# MCU_POWER.net
KiCad netlist of a schematic drawn in Altium Designer
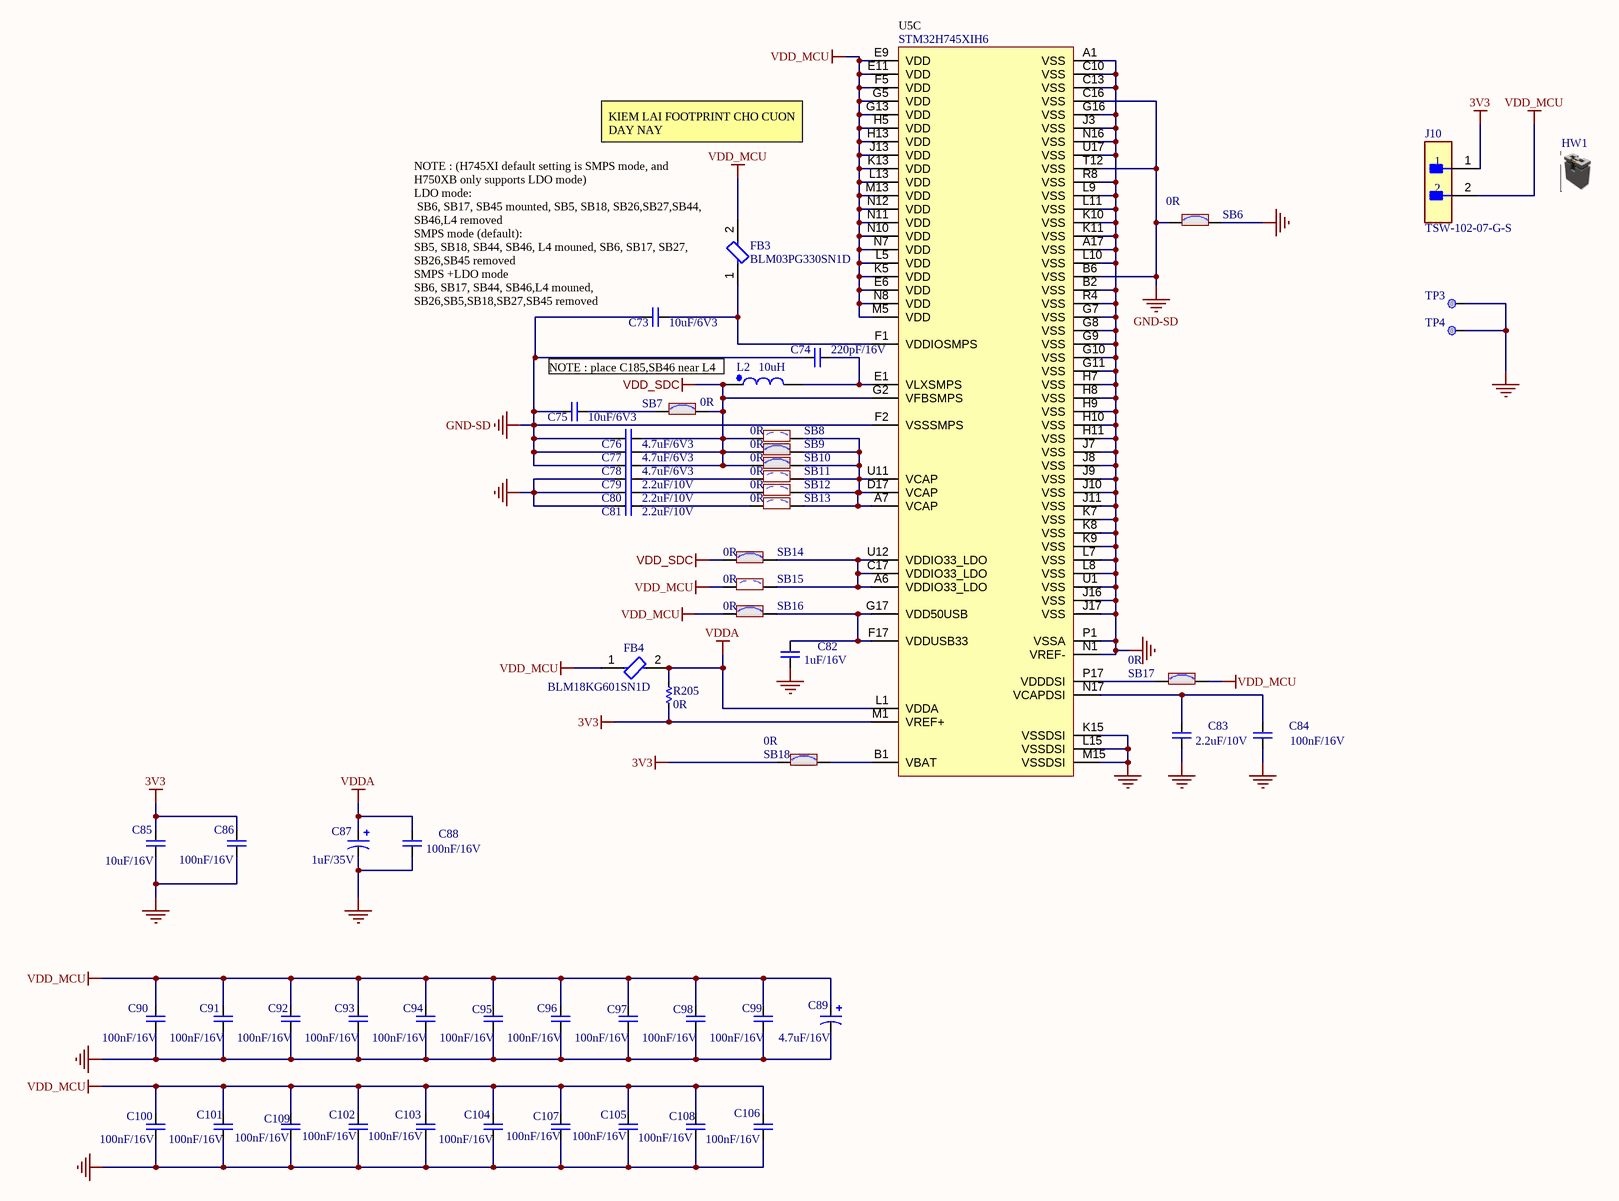
[diagram p0: MCU_POWER.SchDoc]

(export (version "E")
  (design (tool "Eeschema 10.0.6"))
  (components
    (comp (ref "C73")
      (value "10uF/6V3")
      (footprint "CAP_C_1608X80")
      (description "CAP_Chip")
      (libsource (lib "LABLIB") (part "CAP_SMD"))
    )
    (comp (ref "C74")
      (value "220pF/16V")
      (footprint "CAP_C_1608X80")
      (description "CAP_Chip")
      (libsource (lib "LABLIB") (part "CAP_SMD"))
    )
    (comp (ref "C75")
      (value "10uF/6V3")
      (footprint "CAP_C_1608X80")
      (description "CAP_Chip")
      (libsource (lib "LABLIB") (part "CAP_SMD"))
    )
    (comp (ref "C76")
      (value "4.7uF/6V3")
      (footprint "CAP_C_1608X80")
      (description "CAP_Chip")
      (libsource (lib "LABLIB") (part "CAP_SMD"))
    )
    (comp (ref "C77")
      (value "4.7uF/6V3")
      (footprint "CAP_C_1608X80")
      (description "CAP_Chip")
      (libsource (lib "LABLIB") (part "CAP_SMD"))
    )
    (comp (ref "C78")
      (value "4.7uF/6V3")
      (footprint "CAP_C_1608X80")
      (description "CAP_Chip")
      (libsource (lib "LABLIB") (part "CAP_SMD"))
    )
    (comp (ref "C79")
      (value "2.2uF/10V")
      (footprint "CAP_C_1608X80")
      (description "CAP_Chip")
      (libsource (lib "LABLIB") (part "CAP_SMD"))
    )
    (comp (ref "C80")
      (value "2.2uF/10V")
      (footprint "CAP_C_1608X80")
      (description "CAP_Chip")
      (libsource (lib "LABLIB") (part "CAP_SMD"))
    )
    (comp (ref "C81")
      (value "2.2uF/10V")
      (footprint "CAP_C_1608X80")
      (description "CAP_Chip")
      (libsource (lib "LABLIB") (part "CAP_SMD"))
    )
    (comp (ref "C82")
      (value "1uF/16V")
      (footprint "CAP_C_1608X80")
      (description "CAP_Chip")
      (libsource (lib "LABLIB") (part "CAP_SMD"))
    )
    (comp (ref "C83")
      (value "2.2uF/10V")
      (footprint "CAP_C_1608X80")
      (description "CAP_Chip")
      (libsource (lib "LABLIB") (part "CAP_SMD"))
    )
    (comp (ref "C84")
      (value "100nF/16V")
      (footprint "CAP_C_1608X80")
      (description "CAP_Chip")
      (libsource (lib "LABLIB") (part "CAP_SMD"))
    )
    (comp (ref "C85")
      (value "10uF/16V")
      (footprint "CAP_C_1608X80")
      (description "CAP_Chip")
      (libsource (lib "LABLIB") (part "CAP_SMD"))
    )
    (comp (ref "C86")
      (value "100nF/16V")
      (footprint "CAP_C_1608X80")
      (description "CAP_Chip")
      (libsource (lib "LABLIB") (part "CAP_SMD"))
    )
    (comp (ref "C87")
      (value "1uF/35V")
      (footprint "CAP_MP_1608X90")
      (description "CAP Polarization")
      (libsource (lib "LABLIB") (part "_CAP_Pola_2"))
    )
    (comp (ref "C88")
      (value "100nF/16V")
      (footprint "CAP_C_1608X80")
      (description "CAP_Chip")
      (libsource (lib "LABLIB") (part "CAP_SMD"))
    )
    (comp (ref "C89")
      (value "4.7uF/16V")
      (footprint "CAP_MP_1608X90")
      (description "CAP Polarization")
      (libsource (lib "LABLIB") (part "_CAP_Pola_2"))
    )
    (comp (ref "C90")
      (value "100nF/16V")
      (footprint "CAP_C_1608X80")
      (description "CAP_Chip")
      (libsource (lib "LABLIB") (part "CAP_SMD"))
    )
    (comp (ref "C91")
      (value "100nF/16V")
      (footprint "CAP_C_1608X80")
      (description "CAP_Chip")
      (libsource (lib "LABLIB") (part "CAP_SMD"))
    )
    (comp (ref "C92")
      (value "100nF/16V")
      (footprint "CAP_C_1608X80")
      (description "CAP_Chip")
      (libsource (lib "LABLIB") (part "CAP_SMD"))
    )
    (comp (ref "C93")
      (value "100nF/16V")
      (footprint "CAP_C_1608X80")
      (description "CAP_Chip")
      (libsource (lib "LABLIB") (part "CAP_SMD"))
    )
    (comp (ref "C94")
      (value "100nF/16V")
      (footprint "CAP_C_1608X80")
      (description "CAP_Chip")
      (libsource (lib "LABLIB") (part "CAP_SMD"))
    )
    (comp (ref "C95")
      (value "100nF/16V")
      (footprint "CAP_C_1608X80")
      (description "CAP_Chip")
      (libsource (lib "LABLIB") (part "CAP_SMD"))
    )
    (comp (ref "C96")
      (value "100nF/16V")
      (footprint "CAP_C_1608X80")
      (description "CAP_Chip")
      (libsource (lib "LABLIB") (part "CAP_SMD"))
    )
    (comp (ref "C97")
      (value "100nF/16V")
      (footprint "CAP_C_1608X80")
      (description "CAP_Chip")
      (libsource (lib "LABLIB") (part "CAP_SMD"))
    )
    (comp (ref "C98")
      (value "100nF/16V")
      (footprint "CAP_C_1608X80")
      (description "CAP_Chip")
      (libsource (lib "LABLIB") (part "CAP_SMD"))
    )
    (comp (ref "C99")
      (value "100nF/16V")
      (footprint "CAP_C_1608X80")
      (description "CAP_Chip")
      (libsource (lib "LABLIB") (part "CAP_SMD"))
    )
    (comp (ref "C100")
      (value "100nF/16V")
      (footprint "CAP_C_1608X80")
      (description "CAP_Chip")
      (libsource (lib "LABLIB") (part "CAP_SMD"))
    )
    (comp (ref "C101")
      (value "100nF/16V")
      (footprint "CAP_C_1608X80")
      (description "CAP_Chip")
      (libsource (lib "LABLIB") (part "CAP_SMD"))
    )
    (comp (ref "C102")
      (value "100nF/16V")
      (footprint "CAP_C_1608X80")
      (description "CAP_Chip")
      (libsource (lib "LABLIB") (part "CAP_SMD"))
    )
    (comp (ref "C103")
      (value "100nF/16V")
      (footprint "CAP_C_1608X80")
      (description "CAP_Chip")
      (libsource (lib "LABLIB") (part "CAP_SMD"))
    )
    (comp (ref "C104")
      (value "100nF/16V")
      (footprint "CAP_C_1608X80")
      (description "CAP_Chip")
      (libsource (lib "LABLIB") (part "CAP_SMD"))
    )
    (comp (ref "C105")
      (value "100nF/16V")
      (footprint "CAP_C_1608X80")
      (description "CAP_Chip")
      (libsource (lib "LABLIB") (part "CAP_SMD"))
    )
    (comp (ref "C106")
      (value "100nF/16V")
      (footprint "CAP_C_1608X80")
      (description "CAP_Chip")
      (libsource (lib "LABLIB") (part "CAP_SMD"))
    )
    (comp (ref "C107")
      (value "100nF/16V")
      (footprint "CAP_C_1608X80")
      (description "CAP_Chip")
      (libsource (lib "LABLIB") (part "CAP_SMD"))
    )
    (comp (ref "C108")
      (value "100nF/16V")
      (footprint "CAP_C_1608X80")
      (description "CAP_Chip")
      (libsource (lib "LABLIB") (part "CAP_SMD"))
    )
    (comp (ref "C109")
      (value "100nF/16V")
      (footprint "CAP_C_1608X80")
      (description "CAP_Chip")
      (libsource (lib "LABLIB") (part "CAP_SMD"))
    )
    (comp (ref "FB3")
      (value "BLM03PG330SN1D")
      (footprint "FP-BLM03-0_03-d0_3-IPC_C")
      (description "Ferrite Bead, 0201, 33Ω @ 100MHz, 25%, 0.09Ω, 750mA")
      (fields (field (name "TOLERANCE") "25%"))
      (libsource (lib "Altium Content Vault") (part "5f30dd21d616792df468990f7003faa"))
    )
    (comp (ref "FB4")
      (value "BLM18KG601SN1D")
      (footprint "FP-BLM18-0_15-t0_8-IPC_A")
      (description "Chip Ferrite Bead, 0603, 600Ω @ 100MHz, 0.15Ω, 25%, 1.3A")
      (fields (field (name "TOLERANCE") "25%"))
      (libsource (lib "Altium Content Vault") (part "5f30dd21d616792df468990f7003faa"))
    )
    (comp (ref "HW1")
      (value "Shunt 2.54mm")
      (footprint "N/A")
      (description "SHUNT 2.54mm BLACK")
      (fields
        (field (name "INTERNAL_PART_NUMBER") "MCD-00043")
        (field (name "MANUFACTURER_PART_NUMBER") "SNT-100-BK-G")
        (field (name "PROVIDED_BY") "Subcon")
      )
      (libsource (lib "MCD_PARTS_database") (part "Shunt 2.54mm"))
    )
    (comp (ref "J10")
      (value "TSW-102-07-G-S")
      (footprint "FP-TSW-102-07-G-S-MFG")
      (description "CONN HEADER VERT 2POS 2.54MM")
      (fields
        (field (name "MANUFACTURER") "Samtec")
        (field (name "OCTOPART") "https://octopart.com/tsw-102-07-g-s-samtec-272197")
      )
      (libsource (lib "Altium Content Vault") (part "3bc925449376181038e59eaffc5286c"))
    )
    (comp (ref "L2")
      (value "10uH")
      (footprint "INDC1608X95N")
      (description "FIXED IND 10UH 300MA 600MOHM SMD")
      (libsource (lib "LABLIB") (part "_IND"))
    )
    (comp (ref "R205")
      (value "0R")
      (footprint "RES_C_1608X60")
      (description "RES")
      (libsource (lib "LABLIB") (part "_RES_B_2"))
    )
    (comp (ref "SB6")
      (value "0R")
      (footprint "Jump2")
      (description "Solder Bridge ON")
      (fields
        (field (name "INTERNAL_PART_NUMBER") "MCD-00071")
        (field (name "MANUFACTURER") "YAGEO")
        (field (name "PROVIDED_BY") "Subcon")
      )
      (libsource (lib "MCD_PARTS_database") (part "SB_ON"))
    )
    (comp (ref "SB7")
      (value "0R")
      (footprint "Jump2")
      (description "Solder Bridge ON")
      (fields
        (field (name "INTERNAL_PART_NUMBER") "MCD-00071")
        (field (name "MANUFACTURER") "YAGEO")
        (field (name "PROVIDED_BY") "Subcon")
      )
      (libsource (lib "MCD_PARTS_database") (part "SB_ON"))
    )
    (comp (ref "SB8")
      (value "0R")
      (footprint "Jump2")
      (description "Solder Bridge OFF")
      (fields (field (name "INTERNAL_PART_NUMBER") "MCD-00072") (field (name "MANUFACTURER") "YAGEO"))
      (libsource (lib "MCD_PARTS_database") (part "SB_OFF"))
    )
    (comp (ref "SB9")
      (value "0R")
      (footprint "Jump2")
      (description "Solder Bridge ON")
      (fields
        (field (name "INTERNAL_PART_NUMBER") "MCD-00071")
        (field (name "MANUFACTURER") "YAGEO")
        (field (name "PROVIDED_BY") "Subcon")
      )
      (libsource (lib "MCD_PARTS_database") (part "SB_ON"))
    )
    (comp (ref "SB10")
      (value "0R")
      (footprint "Jump2")
      (description "Solder Bridge ON")
      (fields
        (field (name "INTERNAL_PART_NUMBER") "MCD-00071")
        (field (name "MANUFACTURER") "YAGEO")
        (field (name "PROVIDED_BY") "Subcon")
      )
      (libsource (lib "MCD_PARTS_database") (part "SB_ON"))
    )
    (comp (ref "SB11")
      (value "0R")
      (footprint "Jump2")
      (description "Solder Bridge OFF")
      (fields (field (name "INTERNAL_PART_NUMBER") "MCD-00072") (field (name "MANUFACTURER") "YAGEO"))
      (libsource (lib "MCD_PARTS_database") (part "SB_OFF"))
    )
    (comp (ref "SB12")
      (value "0R")
      (footprint "Jump2")
      (description "Solder Bridge OFF")
      (fields (field (name "INTERNAL_PART_NUMBER") "MCD-00072") (field (name "MANUFACTURER") "YAGEO"))
      (libsource (lib "MCD_PARTS_database") (part "SB_OFF"))
    )
    (comp (ref "SB13")
      (value "0R")
      (footprint "Jump2")
      (description "Solder Bridge OFF")
      (fields (field (name "INTERNAL_PART_NUMBER") "MCD-00072") (field (name "MANUFACTURER") "YAGEO"))
      (libsource (lib "MCD_PARTS_database") (part "SB_OFF"))
    )
    (comp (ref "SB14")
      (value "0R")
      (footprint "Jump2")
      (description "Solder Bridge ON")
      (fields
        (field (name "INTERNAL_PART_NUMBER") "MCD-00071")
        (field (name "MANUFACTURER") "YAGEO")
        (field (name "PROVIDED_BY") "Subcon")
      )
      (libsource (lib "MCD_PARTS_database") (part "SB_ON"))
    )
    (comp (ref "SB15")
      (value "0R")
      (footprint "Jump2")
      (description "Solder Bridge OFF")
      (fields (field (name "INTERNAL_PART_NUMBER") "MCD-00072") (field (name "MANUFACTURER") "YAGEO"))
      (libsource (lib "MCD_PARTS_database") (part "SB_OFF"))
    )
    (comp (ref "SB16")
      (value "0R")
      (footprint "Jump2")
      (description "Solder Bridge ON")
      (fields
        (field (name "INTERNAL_PART_NUMBER") "MCD-00071")
        (field (name "MANUFACTURER") "YAGEO")
        (field (name "PROVIDED_BY") "Subcon")
      )
      (libsource (lib "MCD_PARTS_database") (part "SB_ON"))
    )
    (comp (ref "SB17")
      (value "0R")
      (footprint "Jump2")
      (description "Solder Bridge ON")
      (fields
        (field (name "INTERNAL_PART_NUMBER") "MCD-00071")
        (field (name "MANUFACTURER") "YAGEO")
        (field (name "PROVIDED_BY") "Subcon")
      )
      (libsource (lib "MCD_PARTS_database") (part "SB_ON"))
    )
    (comp (ref "SB18")
      (value "0R")
      (footprint "Jump2")
      (description "Solder Bridge ON")
      (fields
        (field (name "INTERNAL_PART_NUMBER") "MCD-00071")
        (field (name "MANUFACTURER") "YAGEO")
        (field (name "PROVIDED_BY") "Subcon")
      )
      (libsource (lib "MCD_PARTS_database") (part "SB_ON"))
    )
    (comp (ref "TP3")
      (value "Test Point")
      (footprint "TESTPOINT")
      (description "Test Point 0.3mm")
      (fields (field (name "INTERNAL_PART_NUMBER") "MCD-00630"))
      (libsource (lib "MCD_PARTS_database") (part "Test Point"))
    )
    (comp (ref "TP4")
      (value "Test Point")
      (footprint "TESTPOINT")
      (description "Test Point 0.3mm")
      (fields (field (name "INTERNAL_PART_NUMBER") "MCD-00630"))
      (libsource (lib "MCD_PARTS_database") (part "Test Point"))
    )
    (comp (ref "U5")
      (value "STM32H745XIH6")
      (footprint "TFBGA240+25")
      (description "32bit MCU TFBGA240+25")
      (fields
        (field (name "INTERNAL_PART_NUMBER") "MCD-01085")
        (field (name "MANUFACTURER") "STMICROELECTRONICS")
        (field (name "PROVIDED_BY") "STM")
      )
      (libsource (lib "MCD_PARTS_database") (part "STM32H745XIH6"))
    )
  )
  (nets
    (net (code "1") (name "3V3") (class "Default")
      (node (ref "C85") (pin "2") (pinfunction "2_2") (pintype "passive"))
      (node (ref "C86") (pin "2") (pinfunction "2_2") (pintype "passive"))
      (node (ref "J10") (pin "1") (pinfunction "1_1") (pintype "passive"))
      (node (ref "R205") (pin "1") (pinfunction "1_1") (pintype "passive"))
      (node (ref "SB18") (pin "1") (pinfunction "1_1") (pintype "passive"))
      (node (ref "U5") (pin "M1") (pinfunction "VREF+_M1") (pintype "passive"))
    )
    (net (code "2") (name "GND") (class "Default")
      (node (ref "C100") (pin "1") (pinfunction "1_1") (pintype "passive"))
      (node (ref "C101") (pin "1") (pinfunction "1_1") (pintype "passive"))
      (node (ref "C102") (pin "1") (pinfunction "1_1") (pintype "passive"))
      (node (ref "C103") (pin "1") (pinfunction "1_1") (pintype "passive"))
      (node (ref "C104") (pin "1") (pinfunction "1_1") (pintype "passive"))
      (node (ref "C105") (pin "1") (pinfunction "1_1") (pintype "passive"))
      (node (ref "C106") (pin "1") (pinfunction "1_1") (pintype "passive"))
      (node (ref "C107") (pin "1") (pinfunction "1_1") (pintype "passive"))
      (node (ref "C108") (pin "1") (pinfunction "1_1") (pintype "passive"))
      (node (ref "C109") (pin "1") (pinfunction "1_1") (pintype "passive"))
      (node (ref "C79") (pin "2") (pinfunction "2_2") (pintype "passive"))
      (node (ref "C80") (pin "2") (pinfunction "2_2") (pintype "passive"))
      (node (ref "C81") (pin "2") (pinfunction "2_2") (pintype "passive"))
      (node (ref "C82") (pin "1") (pinfunction "1_1") (pintype "passive"))
      (node (ref "C83") (pin "1") (pinfunction "1_1") (pintype "passive"))
      (node (ref "C84") (pin "1") (pinfunction "1_1") (pintype "passive"))
      (node (ref "C85") (pin "1") (pinfunction "1_1") (pintype "passive"))
      (node (ref "C86") (pin "1") (pinfunction "1_1") (pintype "passive"))
      (node (ref "C87") (pin "2") (pinfunction "2_2") (pintype "passive"))
      (node (ref "C88") (pin "1") (pinfunction "1_1") (pintype "passive"))
      (node (ref "C89") (pin "2") (pinfunction "2_2") (pintype "passive"))
      (node (ref "C90") (pin "1") (pinfunction "1_1") (pintype "passive"))
      (node (ref "C91") (pin "1") (pinfunction "1_1") (pintype "passive"))
      (node (ref "C92") (pin "1") (pinfunction "1_1") (pintype "passive"))
      (node (ref "C93") (pin "1") (pinfunction "1_1") (pintype "passive"))
      (node (ref "C94") (pin "1") (pinfunction "1_1") (pintype "passive"))
      (node (ref "C95") (pin "1") (pinfunction "1_1") (pintype "passive"))
      (node (ref "C96") (pin "1") (pinfunction "1_1") (pintype "passive"))
      (node (ref "C97") (pin "1") (pinfunction "1_1") (pintype "passive"))
      (node (ref "C98") (pin "1") (pinfunction "1_1") (pintype "passive"))
      (node (ref "C99") (pin "1") (pinfunction "1_1") (pintype "passive"))
      (node (ref "SB6") (pin "2") (pinfunction "2_2") (pintype "passive"))
      (node (ref "TP3") (pin "1") (pinfunction "1_1") (pintype "passive"))
      (node (ref "TP4") (pin "1") (pinfunction "1_1") (pintype "passive"))
      (node (ref "U5") (pin "A1") (pinfunction "VSS_A1") (pintype "passive"))
      (node (ref "U5") (pin "A17") (pinfunction "VSS_A17") (pintype "passive"))
      (node (ref "U5") (pin "B2") (pinfunction "VSS_B2") (pintype "passive"))
      (node (ref "U5") (pin "C10") (pinfunction "VSS_C10") (pintype "passive"))
      (node (ref "U5") (pin "C13") (pinfunction "VSS_C13") (pintype "passive"))
      (node (ref "U5") (pin "G10") (pinfunction "VSS_G10") (pintype "passive"))
      (node (ref "U5") (pin "G11") (pinfunction "VSS_G11") (pintype "passive"))
      (node (ref "U5") (pin "G16") (pinfunction "VSS_G16") (pintype "passive"))
      (node (ref "U5") (pin "G7") (pinfunction "VSS_G7") (pintype "passive"))
      (node (ref "U5") (pin "G8") (pinfunction "VSS_G8") (pintype "passive"))
      (node (ref "U5") (pin "G9") (pinfunction "VSS_G9") (pintype "passive"))
      (node (ref "U5") (pin "H10") (pinfunction "VSS_H10") (pintype "passive"))
      (node (ref "U5") (pin "H11") (pinfunction "VSS_H11") (pintype "passive"))
      (node (ref "U5") (pin "H7") (pinfunction "VSS_H7") (pintype "passive"))
      (node (ref "U5") (pin "H8") (pinfunction "VSS_H8") (pintype "passive"))
      (node (ref "U5") (pin "H9") (pinfunction "VSS_H9") (pintype "passive"))
      (node (ref "U5") (pin "J10") (pinfunction "VSS_J10") (pintype "passive"))
      (node (ref "U5") (pin "J11") (pinfunction "VSS_J11") (pintype "passive"))
      (node (ref "U5") (pin "J16") (pinfunction "VSS_J16") (pintype "passive"))
      (node (ref "U5") (pin "J17") (pinfunction "VSS_J17") (pintype "passive"))
      (node (ref "U5") (pin "J3") (pinfunction "VSS_J3") (pintype "passive"))
      (node (ref "U5") (pin "J7") (pinfunction "VSS_J7") (pintype "passive"))
      (node (ref "U5") (pin "J8") (pinfunction "VSS_J8") (pintype "passive"))
      (node (ref "U5") (pin "J9") (pinfunction "VSS_J9") (pintype "passive"))
      (node (ref "U5") (pin "K10") (pinfunction "VSS_K10") (pintype "passive"))
      (node (ref "U5") (pin "K11") (pinfunction "VSS_K11") (pintype "passive"))
      (node (ref "U5") (pin "K15") (pinfunction "VSSDSI_K15") (pintype "passive"))
      (node (ref "U5") (pin "K7") (pinfunction "VSS_K7") (pintype "passive"))
      (node (ref "U5") (pin "K8") (pinfunction "VSS_K8") (pintype "passive"))
      (node (ref "U5") (pin "K9") (pinfunction "VSS_K9") (pintype "passive"))
      (node (ref "U5") (pin "L10") (pinfunction "VSS_L10") (pintype "passive"))
      (node (ref "U5") (pin "L11") (pinfunction "VSS_L11") (pintype "passive"))
      (node (ref "U5") (pin "L15") (pinfunction "VSSDSI_L15") (pintype "passive"))
      (node (ref "U5") (pin "L7") (pinfunction "VSS_L7") (pintype "passive"))
      (node (ref "U5") (pin "L8") (pinfunction "VSS_L8") (pintype "passive"))
      (node (ref "U5") (pin "L9") (pinfunction "VSS_L9") (pintype "passive"))
      (node (ref "U5") (pin "M15") (pinfunction "VSSDSI_M15") (pintype "passive"))
      (node (ref "U5") (pin "N1") (pinfunction "VREF-_N1") (pintype "passive"))
      (node (ref "U5") (pin "N16") (pinfunction "VSS_N16") (pintype "passive"))
      (node (ref "U5") (pin "P1") (pinfunction "VSSA_P1") (pintype "passive"))
      (node (ref "U5") (pin "R4") (pinfunction "VSS_R4") (pintype "passive"))
      (node (ref "U5") (pin "R8") (pinfunction "VSS_R8") (pintype "passive"))
      (node (ref "U5") (pin "U1") (pinfunction "VSS_U1") (pintype "passive"))
      (node (ref "U5") (pin "U17") (pinfunction "VSS_U17") (pintype "passive"))
    )
    (net (code "3") (name "GND-SD") (class "Default")
      (node (ref "C73") (pin "2") (pinfunction "2_2") (pintype "passive"))
      (node (ref "C74") (pin "2") (pinfunction "2_2") (pintype "passive"))
      (node (ref "C75") (pin "2") (pinfunction "2_2") (pintype "passive"))
      (node (ref "C76") (pin "2") (pinfunction "2_2") (pintype "passive"))
      (node (ref "C77") (pin "2") (pinfunction "2_2") (pintype "passive"))
      (node (ref "C78") (pin "2") (pinfunction "2_2") (pintype "passive"))
      (node (ref "SB6") (pin "1") (pinfunction "1_1") (pintype "passive"))
      (node (ref "U5") (pin "B6") (pinfunction "VSS_B6") (pintype "passive"))
      (node (ref "U5") (pin "C16") (pinfunction "VSS_C16") (pintype "passive"))
      (node (ref "U5") (pin "F2") (pinfunction "VSSSMPS_F2") (pintype "passive"))
      (node (ref "U5") (pin "T12") (pinfunction "VSS_T12") (pintype "passive"))
    )
    (net (code "4") (name "Net-(C75-Pad1)") (class "Default")
      (node (ref "C75") (pin "1") (pinfunction "1_1") (pintype "passive"))
      (node (ref "SB7") (pin "1") (pinfunction "1_1") (pintype "passive"))
    )
    (net (code "5") (name "Net-(C79-Pad1)") (class "Default")
      (node (ref "C79") (pin "1") (pinfunction "1_1") (pintype "passive"))
      (node (ref "SB11") (pin "1") (pinfunction "1_1") (pintype "passive"))
    )
    (net (code "6") (name "Net-(C80-Pad1)") (class "Default")
      (node (ref "C80") (pin "1") (pinfunction "1_1") (pintype "passive"))
      (node (ref "SB12") (pin "1") (pinfunction "1_1") (pintype "passive"))
    )
    (net (code "7") (name "Net-(C81-Pad1)") (class "Default")
      (node (ref "C81") (pin "1") (pinfunction "1_1") (pintype "passive"))
      (node (ref "SB13") (pin "1") (pinfunction "1_1") (pintype "passive"))
    )
    (net (code "8") (name "Net-(SB10-Pad2)") (class "Default")
      (node (ref "SB10") (pin "2") (pinfunction "2_2") (pintype "passive"))
      (node (ref "SB11") (pin "2") (pinfunction "2_2") (pintype "passive"))
      (node (ref "SB12") (pin "2") (pinfunction "2_2") (pintype "passive"))
      (node (ref "SB13") (pin "2") (pinfunction "2_2") (pintype "passive"))
      (node (ref "SB8") (pin "2") (pinfunction "2_2") (pintype "passive"))
      (node (ref "SB9") (pin "2") (pinfunction "2_2") (pintype "passive"))
      (node (ref "U5") (pin "A7") (pinfunction "VCAP_A7") (pintype "passive"))
      (node (ref "U5") (pin "D17") (pinfunction "VCAP_D17") (pintype "passive"))
      (node (ref "U5") (pin "U11") (pinfunction "VCAP_U11") (pintype "passive"))
    )
    (net (code "9") (name "Net-(SB14-Pad2)") (class "Default")
      (node (ref "SB14") (pin "2") (pinfunction "2_2") (pintype "passive"))
      (node (ref "SB15") (pin "2") (pinfunction "2_2") (pintype "passive"))
      (node (ref "U5") (pin "A6") (pinfunction "VDDIO33_LDO_A6") (pintype "passive"))
      (node (ref "U5") (pin "C17") (pinfunction "VDDIO33_LDO_C17") (pintype "passive"))
      (node (ref "U5") (pin "U12") (pinfunction "VDDIO33_LDO_U12") (pintype "passive"))
    )
    (net (code "10") (name "Net-(U5C-VBAT)") (class "Default")
      (node (ref "SB18") (pin "2") (pinfunction "2_2") (pintype "passive"))
      (node (ref "U5") (pin "B1") (pinfunction "VBAT_B1") (pintype "passive"))
    )
    (net (code "11") (name "Net-(U5C-VCAPDSI)") (class "Default")
      (node (ref "C83") (pin "2") (pinfunction "2_2") (pintype "passive"))
      (node (ref "C84") (pin "2") (pinfunction "2_2") (pintype "passive"))
      (node (ref "U5") (pin "N17") (pinfunction "VCAPDSI_N17") (pintype "passive"))
    )
    (net (code "12") (name "Net-(U5C-VDD50USB)") (class "Default")
      (node (ref "C82") (pin "2") (pinfunction "2_2") (pintype "passive"))
      (node (ref "SB16") (pin "2") (pinfunction "2_2") (pintype "passive"))
      (node (ref "U5") (pin "F17") (pinfunction "VDDUSB33_F17") (pintype "passive"))
      (node (ref "U5") (pin "G17") (pinfunction "VDD50USB_G17") (pintype "passive"))
    )
    (net (code "13") (name "Net-(U5C-VDDDSI)") (class "Default")
      (node (ref "SB17") (pin "1") (pinfunction "1_1") (pintype "passive"))
      (node (ref "U5") (pin "P17") (pinfunction "VDDDSI_P17") (pintype "passive"))
    )
    (net (code "14") (name "Net-(U5C-VDDIOSMPS)") (class "Default")
      (node (ref "C73") (pin "1") (pinfunction "1_1") (pintype "passive"))
      (node (ref "FB3") (pin "1") (pinfunction "1_1") (pintype "passive"))
      (node (ref "U5") (pin "F1") (pinfunction "VDDIOSMPS_F1") (pintype "passive"))
    )
    (net (code "15") (name "Net-(U5C-VLXSMPS)") (class "Default")
      (node (ref "C74") (pin "1") (pinfunction "1_1") (pintype "passive"))
      (node (ref "L2") (pin "2") (pinfunction "2_2") (pintype "passive"))
      (node (ref "U5") (pin "E1") (pinfunction "VLXSMPS_E1") (pintype "passive"))
    )
    (net (code "16") (name "VDDA") (class "Default")
      (node (ref "C87") (pin "1") (pinfunction "1_1") (pintype "passive"))
      (node (ref "C88") (pin "2") (pinfunction "2_2") (pintype "passive"))
      (node (ref "FB4") (pin "2") (pinfunction "2_2") (pintype "passive"))
      (node (ref "R205") (pin "2") (pinfunction "2_2") (pintype "passive"))
      (node (ref "U5") (pin "L1") (pinfunction "VDDA_L1") (pintype "passive"))
    )
    (net (code "17") (name "VDD_MCU") (class "Default")
      (node (ref "C100") (pin "2") (pinfunction "2_2") (pintype "passive"))
      (node (ref "C101") (pin "2") (pinfunction "2_2") (pintype "passive"))
      (node (ref "C102") (pin "2") (pinfunction "2_2") (pintype "passive"))
      (node (ref "C103") (pin "2") (pinfunction "2_2") (pintype "passive"))
      (node (ref "C104") (pin "2") (pinfunction "2_2") (pintype "passive"))
      (node (ref "C105") (pin "2") (pinfunction "2_2") (pintype "passive"))
      (node (ref "C106") (pin "2") (pinfunction "2_2") (pintype "passive"))
      (node (ref "C107") (pin "2") (pinfunction "2_2") (pintype "passive"))
      (node (ref "C108") (pin "2") (pinfunction "2_2") (pintype "passive"))
      (node (ref "C109") (pin "2") (pinfunction "2_2") (pintype "passive"))
      (node (ref "C89") (pin "1") (pinfunction "1_1") (pintype "passive"))
      (node (ref "C90") (pin "2") (pinfunction "2_2") (pintype "passive"))
      (node (ref "C91") (pin "2") (pinfunction "2_2") (pintype "passive"))
      (node (ref "C92") (pin "2") (pinfunction "2_2") (pintype "passive"))
      (node (ref "C93") (pin "2") (pinfunction "2_2") (pintype "passive"))
      (node (ref "C94") (pin "2") (pinfunction "2_2") (pintype "passive"))
      (node (ref "C95") (pin "2") (pinfunction "2_2") (pintype "passive"))
      (node (ref "C96") (pin "2") (pinfunction "2_2") (pintype "passive"))
      (node (ref "C97") (pin "2") (pinfunction "2_2") (pintype "passive"))
      (node (ref "C98") (pin "2") (pinfunction "2_2") (pintype "passive"))
      (node (ref "C99") (pin "2") (pinfunction "2_2") (pintype "passive"))
      (node (ref "FB3") (pin "2") (pinfunction "2_2") (pintype "passive"))
      (node (ref "FB4") (pin "1") (pinfunction "1_1") (pintype "passive"))
      (node (ref "J10") (pin "2") (pinfunction "2_2") (pintype "passive"))
      (node (ref "SB15") (pin "1") (pinfunction "1_1") (pintype "passive"))
      (node (ref "SB16") (pin "1") (pinfunction "1_1") (pintype "passive"))
      (node (ref "SB17") (pin "2") (pinfunction "2_2") (pintype "passive"))
      (node (ref "U5") (pin "E11") (pinfunction "VDD_E11") (pintype "passive"))
      (node (ref "U5") (pin "E6") (pinfunction "VDD_E6") (pintype "passive"))
      (node (ref "U5") (pin "E9") (pinfunction "VDD_E9") (pintype "passive"))
      (node (ref "U5") (pin "F5") (pinfunction "VDD_F5") (pintype "passive"))
      (node (ref "U5") (pin "G13") (pinfunction "VDD_G13") (pintype "passive"))
      (node (ref "U5") (pin "G5") (pinfunction "VDD_G5") (pintype "passive"))
      (node (ref "U5") (pin "H13") (pinfunction "VDD_H13") (pintype "passive"))
      (node (ref "U5") (pin "H5") (pinfunction "VDD_H5") (pintype "passive"))
      (node (ref "U5") (pin "J13") (pinfunction "VDD_J13") (pintype "passive"))
      (node (ref "U5") (pin "K13") (pinfunction "VDD_K13") (pintype "passive"))
      (node (ref "U5") (pin "K5") (pinfunction "VDD_K5") (pintype "passive"))
      (node (ref "U5") (pin "L13") (pinfunction "VDD_L13") (pintype "passive"))
      (node (ref "U5") (pin "L5") (pinfunction "VDD_L5") (pintype "passive"))
      (node (ref "U5") (pin "M13") (pinfunction "VDD_M13") (pintype "passive"))
      (node (ref "U5") (pin "M5") (pinfunction "VDD_M5") (pintype "passive"))
      (node (ref "U5") (pin "N10") (pinfunction "VDD_N10") (pintype "passive"))
      (node (ref "U5") (pin "N11") (pinfunction "VDD_N11") (pintype "passive"))
      (node (ref "U5") (pin "N12") (pinfunction "VDD_N12") (pintype "passive"))
      (node (ref "U5") (pin "N7") (pinfunction "VDD_N7") (pintype "passive"))
      (node (ref "U5") (pin "N8") (pinfunction "VDD_N8") (pintype "passive"))
    )
    (net (code "18") (name "VDD_SDC") (class "Default")
      (node (ref "C76") (pin "1") (pinfunction "1_1") (pintype "passive"))
      (node (ref "C77") (pin "1") (pinfunction "1_1") (pintype "passive"))
      (node (ref "C78") (pin "1") (pinfunction "1_1") (pintype "passive"))
      (node (ref "L2") (pin "1") (pinfunction "1_1") (pintype "passive"))
      (node (ref "SB10") (pin "1") (pinfunction "1_1") (pintype "passive"))
      (node (ref "SB14") (pin "1") (pinfunction "1_1") (pintype "passive"))
      (node (ref "SB7") (pin "2") (pinfunction "2_2") (pintype "passive"))
      (node (ref "SB8") (pin "1") (pinfunction "1_1") (pintype "passive"))
      (node (ref "SB9") (pin "1") (pinfunction "1_1") (pintype "passive"))
      (node (ref "U5") (pin "G2") (pinfunction "VFBSMPS_G2") (pintype "passive"))
    )
  )
)
